# External_Camera_HAT_LvlShifters.net
KiCad netlist of a schematic drawn in Altium Designer
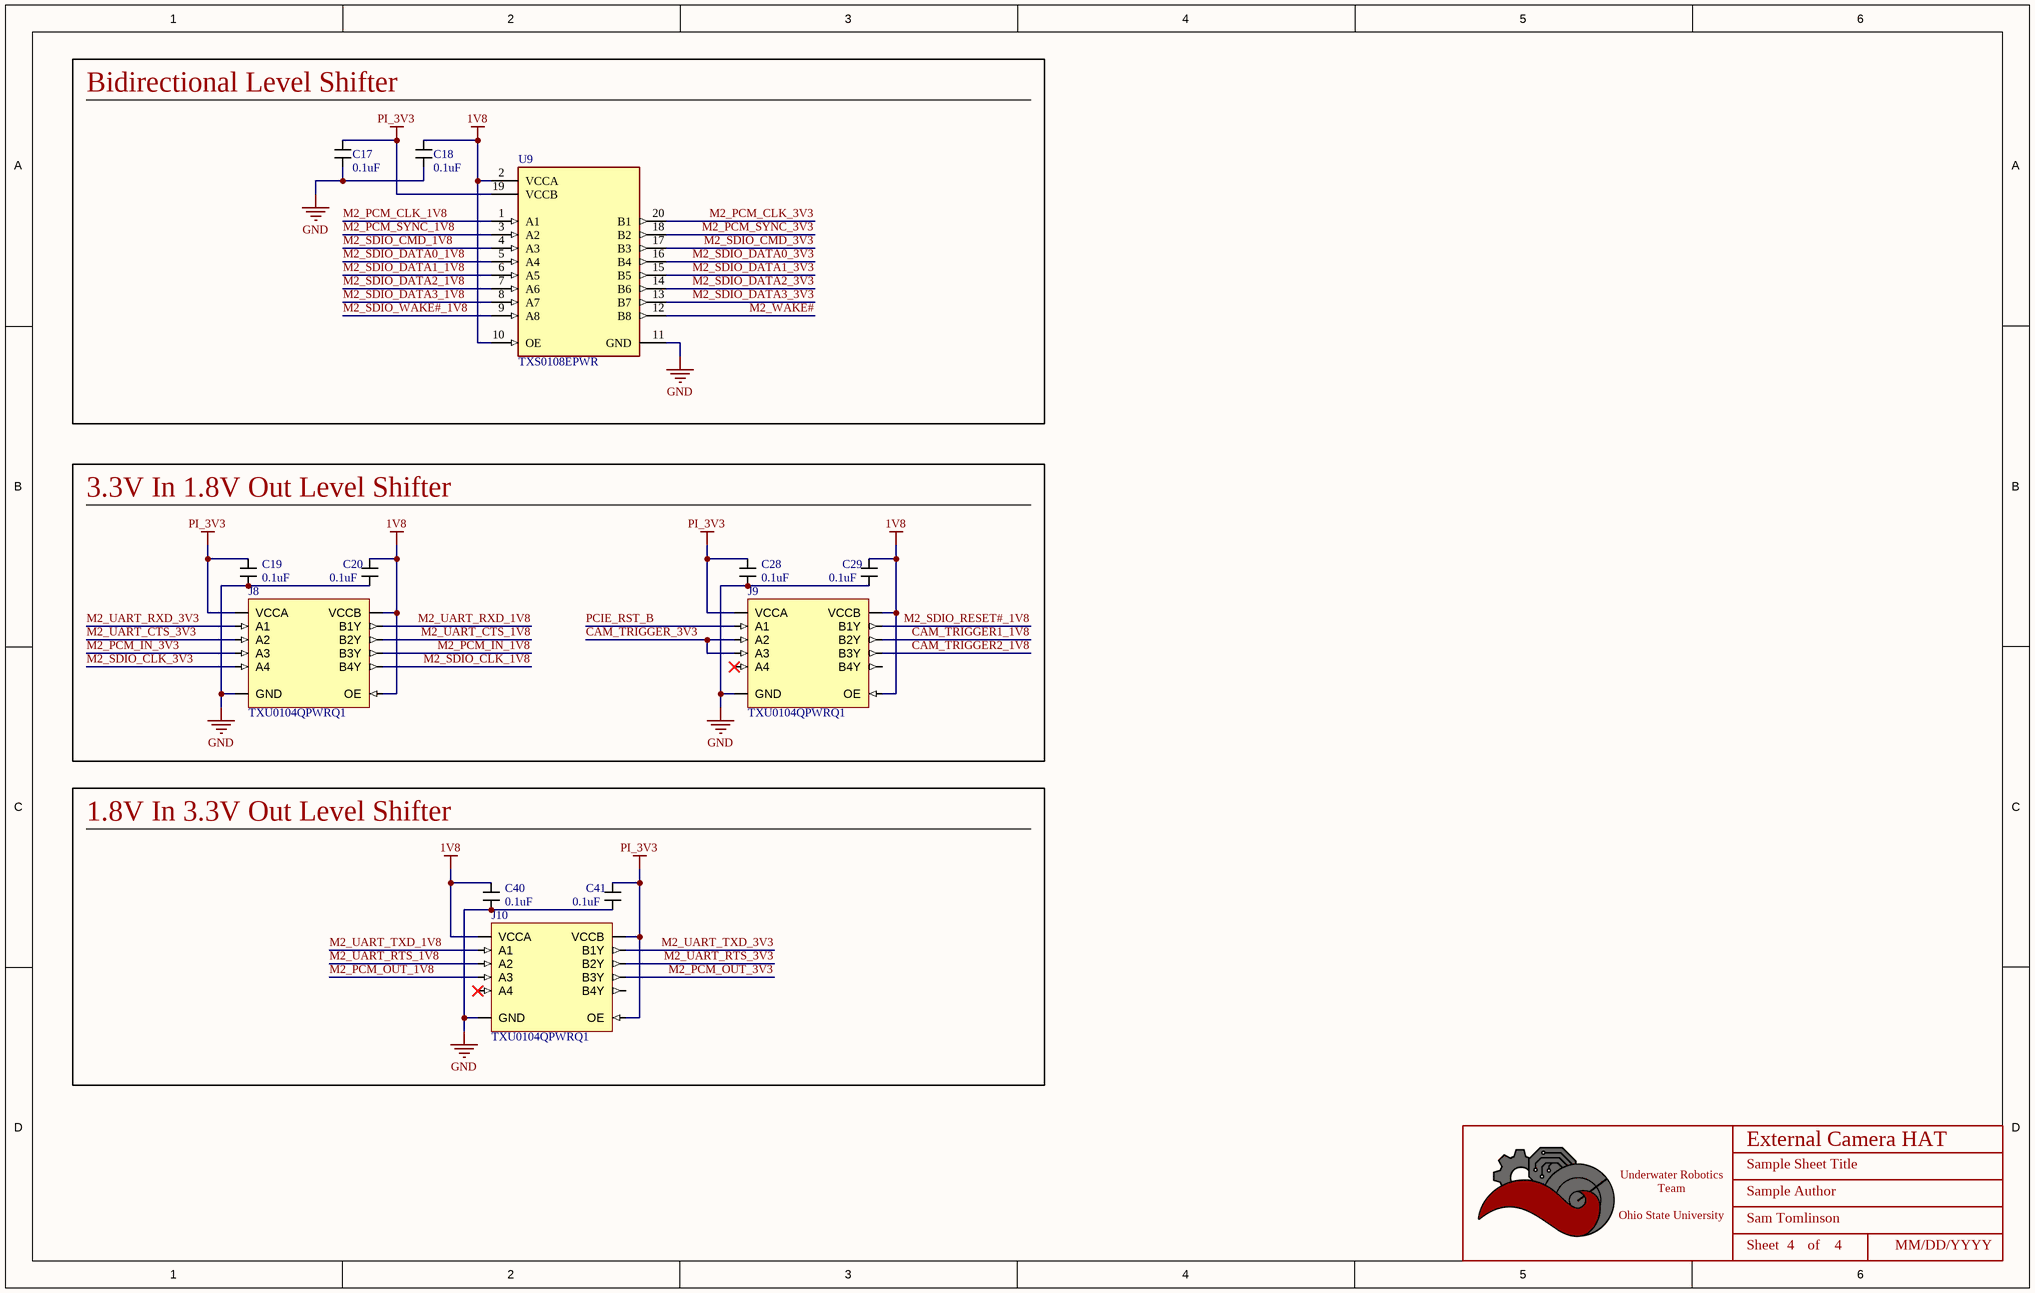
[diagram p0: External_Camera_HAT_LvlShifters.SchDoc]

(export (version "E")
  (design (tool "Eeschema 10.0.6"))
  (components
    (comp (ref "C17")
      (value "0.1uF")
      (footprint "CAPACITOR_0402")
      (description "Cap 100nF 25V +/-10%\r\nCeramic 0402")
      (fields
        (field (name "TOLERANCE") "+/- 10%")
        (field (name "VOLTAGE") "25V")
        (field (name "MADE BY") "Robert Pafford")
      )
      (libsource (lib "Capacitors") (part "CAPACITOR_0.1uF_0402"))
    )
    (comp (ref "C18")
      (value "0.1uF")
      (footprint "CAPACITOR_0402")
      (description "Cap 100nF 25V +/-10%\r\nCeramic 0402")
      (fields
        (field (name "TOLERANCE") "+/- 10%")
        (field (name "VOLTAGE") "25V")
        (field (name "MADE BY") "Robert Pafford")
      )
      (libsource (lib "Capacitors") (part "CAPACITOR_0.1uF_0402"))
    )
    (comp (ref "C19")
      (value "0.1uF")
      (footprint "CAPACITOR_0402")
      (description "Cap 100nF 25V +/-10%\r\nCeramic 0402")
      (fields
        (field (name "TOLERANCE") "+/- 10%")
        (field (name "VOLTAGE") "25V")
        (field (name "MADE BY") "Robert Pafford")
      )
      (libsource (lib "Capacitors") (part "CAPACITOR_0.1uF_0402"))
    )
    (comp (ref "C20")
      (value "0.1uF")
      (footprint "CAPACITOR_0402")
      (description "Cap 100nF 25V +/-10%\r\nCeramic 0402")
      (fields
        (field (name "TOLERANCE") "+/- 10%")
        (field (name "VOLTAGE") "25V")
        (field (name "MADE BY") "Robert Pafford")
      )
      (libsource (lib "Capacitors") (part "CAPACITOR_0.1uF_0402"))
    )
    (comp (ref "C28")
      (value "0.1uF")
      (footprint "CAPACITOR_0402")
      (description "Cap 100nF 25V +/-10%\r\nCeramic 0402")
      (fields
        (field (name "TOLERANCE") "+/- 10%")
        (field (name "VOLTAGE") "25V")
        (field (name "MADE BY") "Robert Pafford")
      )
      (libsource (lib "Capacitors") (part "CAPACITOR_0.1uF_0402"))
    )
    (comp (ref "C29")
      (value "0.1uF")
      (footprint "CAPACITOR_0402")
      (description "Cap 100nF 25V +/-10%\r\nCeramic 0402")
      (fields
        (field (name "TOLERANCE") "+/- 10%")
        (field (name "VOLTAGE") "25V")
        (field (name "MADE BY") "Robert Pafford")
      )
      (libsource (lib "Capacitors") (part "CAPACITOR_0.1uF_0402"))
    )
    (comp (ref "C40")
      (value "0.1uF")
      (footprint "CAPACITOR_0402")
      (description "Cap 100nF 25V +/-10%\r\nCeramic 0402")
      (fields
        (field (name "TOLERANCE") "+/- 10%")
        (field (name "VOLTAGE") "25V")
        (field (name "MADE BY") "Robert Pafford")
      )
      (libsource (lib "Capacitors") (part "CAPACITOR_0.1uF_0402"))
    )
    (comp (ref "C41")
      (value "0.1uF")
      (footprint "CAPACITOR_0402")
      (description "Cap 100nF 25V +/-10%\r\nCeramic 0402")
      (fields
        (field (name "TOLERANCE") "+/- 10%")
        (field (name "VOLTAGE") "25V")
        (field (name "MADE BY") "Robert Pafford")
      )
      (libsource (lib "Capacitors") (part "CAPACITOR_0.1uF_0402"))
    )
    (comp (ref "J8")
      (value "TXU0104QPWRQ1")
      (footprint "PW (R-PDSO-G14)")
      (description "Voltage Level Translator Unidirectional 1 Circuit 4 Channel 200Mbps 14-TSSOP")
      (fields (field (name "MADE BY") "Robert Pafford"))
      (libsource (lib "Integrated Circuits") (part "TXU0104QPWRQ1"))
    )
    (comp (ref "J9")
      (value "TXU0104QPWRQ1")
      (footprint "PW (R-PDSO-G14)")
      (description "Voltage Level Translator Unidirectional 1 Circuit 4 Channel 200Mbps 14-TSSOP")
      (fields (field (name "MADE BY") "Robert Pafford"))
      (libsource (lib "Integrated Circuits") (part "TXU0104QPWRQ1"))
    )
    (comp (ref "J10")
      (value "TXU0104QPWRQ1")
      (footprint "PW (R-PDSO-G14)")
      (description "Voltage Level Translator Unidirectional 1 Circuit 4 Channel 200Mbps 14-TSSOP")
      (fields (field (name "MADE BY") "Robert Pafford"))
      (libsource (lib "Integrated Circuits") (part "TXU0104QPWRQ1"))
    )
    (comp (ref "U9")
      (value "TXS0108EPWR")
      (footprint "FP-PW0020A-IPC_C")
      (description "IC TRNSLTR BIDIRECTIONAL 20TSSOP")
      (libsource (lib "Altium Content Vault") (part "86128ddf5852d4e934b2dd0188c13f1"))
    )
  )
  (nets
    (net (code "1") (name "/CAM_TRIGGER1_1V8") (class "Default")
      (node (ref "J9") (pin "12") (pinfunction "B2Y_12") (pintype "output"))
    )
    (net (code "2") (name "/CAM_TRIGGER2_1V8") (class "Default")
      (node (ref "J9") (pin "11") (pinfunction "B3Y_11") (pintype "output"))
    )
    (net (code "3") (name "/CAM_TRIGGER_3V3") (class "Default")
      (node (ref "J9") (pin "3") (pinfunction "A2_3") (pintype "input"))
      (node (ref "J9") (pin "4") (pinfunction "A3_4") (pintype "input"))
    )
    (net (code "4") (name "/M2_PCM_CLK_1V8") (class "Default")
      (node (ref "U9") (pin "1") (pinfunction "A1_1") (pintype "input"))
    )
    (net (code "5") (name "/M2_PCM_CLK_3V3") (class "Default")
      (node (ref "U9") (pin "20") (pinfunction "B1_20") (pintype "output"))
    )
    (net (code "6") (name "/M2_PCM_IN_1V8") (class "Default")
      (node (ref "J8") (pin "11") (pinfunction "B3Y_11") (pintype "output"))
    )
    (net (code "7") (name "/M2_PCM_IN_3V3") (class "Default")
      (node (ref "J8") (pin "4") (pinfunction "A3_4") (pintype "input"))
    )
    (net (code "8") (name "/M2_PCM_OUT_1V8") (class "Default")
      (node (ref "J10") (pin "4") (pinfunction "A3_4") (pintype "input"))
    )
    (net (code "9") (name "/M2_PCM_OUT_3V3") (class "Default")
      (node (ref "J10") (pin "11") (pinfunction "B3Y_11") (pintype "output"))
    )
    (net (code "10") (name "/M2_PCM_SYNC_1V8") (class "Default")
      (node (ref "U9") (pin "3") (pinfunction "A2_3") (pintype "input"))
    )
    (net (code "11") (name "/M2_PCM_SYNC_3V3") (class "Default")
      (node (ref "U9") (pin "18") (pinfunction "B2_18") (pintype "output"))
    )
    (net (code "12") (name "/M2_SDIO_CLK_1V8") (class "Default")
      (node (ref "J8") (pin "10") (pinfunction "B4Y_10") (pintype "output"))
    )
    (net (code "13") (name "/M2_SDIO_CLK_3V3") (class "Default")
      (node (ref "J8") (pin "5") (pinfunction "A4_5") (pintype "input"))
    )
    (net (code "14") (name "/M2_SDIO_CMD_1V8") (class "Default")
      (node (ref "U9") (pin "4") (pinfunction "A3_4") (pintype "input"))
    )
    (net (code "15") (name "/M2_SDIO_CMD_3V3") (class "Default")
      (node (ref "U9") (pin "17") (pinfunction "B3_17") (pintype "output"))
    )
    (net (code "16") (name "/M2_SDIO_DATA0_1V8") (class "Default")
      (node (ref "U9") (pin "5") (pinfunction "A4_5") (pintype "input"))
    )
    (net (code "17") (name "/M2_SDIO_DATA0_3V3") (class "Default")
      (node (ref "U9") (pin "16") (pinfunction "B4_16") (pintype "output"))
    )
    (net (code "18") (name "/M2_SDIO_DATA1_1V8") (class "Default")
      (node (ref "U9") (pin "6") (pinfunction "A5_6") (pintype "input"))
    )
    (net (code "19") (name "/M2_SDIO_DATA1_3V3") (class "Default")
      (node (ref "U9") (pin "15") (pinfunction "B5_15") (pintype "output"))
    )
    (net (code "20") (name "/M2_SDIO_DATA2_1V8") (class "Default")
      (node (ref "U9") (pin "7") (pinfunction "A6_7") (pintype "input"))
    )
    (net (code "21") (name "/M2_SDIO_DATA2_3V3") (class "Default")
      (node (ref "U9") (pin "14") (pinfunction "B6_14") (pintype "output"))
    )
    (net (code "22") (name "/M2_SDIO_DATA3_1V8") (class "Default")
      (node (ref "U9") (pin "8") (pinfunction "A7_8") (pintype "input"))
    )
    (net (code "23") (name "/M2_SDIO_DATA3_3V3") (class "Default")
      (node (ref "U9") (pin "13") (pinfunction "B7_13") (pintype "output"))
    )
    (net (code "24") (name "/M2_SDIO_RESET#_1V8") (class "Default")
      (node (ref "J9") (pin "13") (pinfunction "B1Y_13") (pintype "output"))
    )
    (net (code "25") (name "/M2_SDIO_WAKE#_1V8") (class "Default")
      (node (ref "U9") (pin "9") (pinfunction "A8_9") (pintype "input"))
    )
    (net (code "26") (name "/M2_UART_CTS_1V8") (class "Default")
      (node (ref "J8") (pin "12") (pinfunction "B2Y_12") (pintype "output"))
    )
    (net (code "27") (name "/M2_UART_CTS_3V3") (class "Default")
      (node (ref "J8") (pin "3") (pinfunction "A2_3") (pintype "input"))
    )
    (net (code "28") (name "/M2_UART_RTS_1V8") (class "Default")
      (node (ref "J10") (pin "3") (pinfunction "A2_3") (pintype "input"))
    )
    (net (code "29") (name "/M2_UART_RTS_3V3") (class "Default")
      (node (ref "J10") (pin "12") (pinfunction "B2Y_12") (pintype "output"))
    )
    (net (code "30") (name "/M2_UART_RXD_1V8") (class "Default")
      (node (ref "J8") (pin "13") (pinfunction "B1Y_13") (pintype "output"))
    )
    (net (code "31") (name "/M2_UART_RXD_3V3") (class "Default")
      (node (ref "J8") (pin "2") (pinfunction "A1_2") (pintype "input"))
    )
    (net (code "32") (name "/M2_UART_TXD_1V8") (class "Default")
      (node (ref "J10") (pin "2") (pinfunction "A1_2") (pintype "input"))
    )
    (net (code "33") (name "/M2_UART_TXD_3V3") (class "Default")
      (node (ref "J10") (pin "13") (pinfunction "B1Y_13") (pintype "output"))
    )
    (net (code "34") (name "/M2_WAKE#") (class "Default")
      (node (ref "U9") (pin "12") (pinfunction "B8_12") (pintype "output"))
    )
    (net (code "35") (name "/PCIE_RST_B") (class "Default")
      (node (ref "J9") (pin "2") (pinfunction "A1_2") (pintype "input"))
    )
    (net (code "36") (name "1V8") (class "Default")
      (node (ref "C18") (pin "1") (pinfunction "1_1") (pintype "passive"))
      (node (ref "C20") (pin "1") (pinfunction "1_1") (pintype "passive"))
      (node (ref "C29") (pin "1") (pinfunction "1_1") (pintype "passive"))
      (node (ref "C40") (pin "1") (pinfunction "1_1") (pintype "passive"))
      (node (ref "J10") (pin "1") (pinfunction "VCCA_1") (pintype "power_in"))
      (node (ref "J8") (pin "14") (pinfunction "VCCB_14") (pintype "power_in"))
      (node (ref "J8") (pin "8") (pinfunction "OE_8") (pintype "input"))
      (node (ref "J9") (pin "14") (pinfunction "VCCB_14") (pintype "power_in"))
      (node (ref "J9") (pin "8") (pinfunction "OE_8") (pintype "input"))
      (node (ref "U9") (pin "10") (pinfunction "OE_10") (pintype "input"))
      (node (ref "U9") (pin "2") (pinfunction "VCCA_2") (pintype "power_in"))
    )
    (net (code "37") (name "GND") (class "Default")
      (node (ref "C17") (pin "2") (pinfunction "2_2") (pintype "passive"))
      (node (ref "C18") (pin "2") (pinfunction "2_2") (pintype "passive"))
      (node (ref "C19") (pin "2") (pinfunction "2_2") (pintype "passive"))
      (node (ref "C20") (pin "2") (pinfunction "2_2") (pintype "passive"))
      (node (ref "C28") (pin "2") (pinfunction "2_2") (pintype "passive"))
      (node (ref "C29") (pin "2") (pinfunction "2_2") (pintype "passive"))
      (node (ref "C40") (pin "2") (pinfunction "2_2") (pintype "passive"))
      (node (ref "C41") (pin "2") (pinfunction "2_2") (pintype "passive"))
      (node (ref "J10") (pin "7") (pinfunction "GND_7") (pintype "power_in"))
      (node (ref "J8") (pin "7") (pinfunction "GND_7") (pintype "power_in"))
      (node (ref "J9") (pin "7") (pinfunction "GND_7") (pintype "power_in"))
      (node (ref "U9") (pin "11") (pinfunction "GND_11") (pintype "power_in"))
    )
    (net (code "38") (name "PI_3V3") (class "Default")
      (node (ref "C17") (pin "1") (pinfunction "1_1") (pintype "passive"))
      (node (ref "C19") (pin "1") (pinfunction "1_1") (pintype "passive"))
      (node (ref "C28") (pin "1") (pinfunction "1_1") (pintype "passive"))
      (node (ref "C41") (pin "1") (pinfunction "1_1") (pintype "passive"))
      (node (ref "J10") (pin "14") (pinfunction "VCCB_14") (pintype "power_in"))
      (node (ref "J10") (pin "8") (pinfunction "OE_8") (pintype "input"))
      (node (ref "J8") (pin "1") (pinfunction "VCCA_1") (pintype "power_in"))
      (node (ref "J9") (pin "1") (pinfunction "VCCA_1") (pintype "power_in"))
      (node (ref "U9") (pin "19") (pinfunction "VCCB_19") (pintype "power_in"))
    )
    (net (code "39") (name "unconnected-(J9-A4-Pad5)") (class "Default")
      (node (ref "J9") (pin "5") (pinfunction "A4_5") (pintype "input+no_connect"))
    )
    (net (code "40") (name "unconnected-(J9-B4Y-Pad10)") (class "Default")
      (node (ref "J9") (pin "10") (pinfunction "B4Y_10") (pintype "output"))
    )
    (net (code "41") (name "unconnected-(J10-A4-Pad5)") (class "Default")
      (node (ref "J10") (pin "5") (pinfunction "A4_5") (pintype "input+no_connect"))
    )
    (net (code "42") (name "unconnected-(J10-B4Y-Pad10)") (class "Default")
      (node (ref "J10") (pin "10") (pinfunction "B4Y_10") (pintype "output"))
    )
  )
)
